# ee107_mcu_fpga_connector_board.net
KiCad netlist of a schematic drawn in Altium Designer
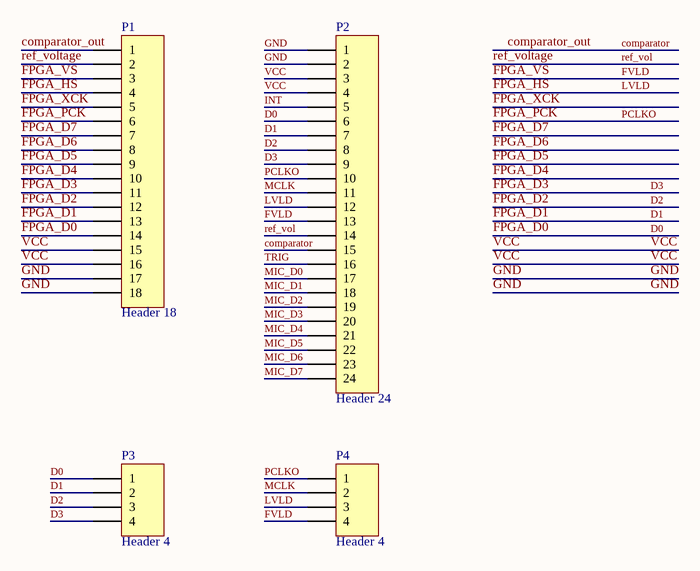
[diagram p0: ee107_mcu_fpga_connector_board.SchDoc]

(export (version "E")
  (design (tool "Eeschema 10.0.6"))
  (components
    (comp (ref "P1")
      (value "Header 18")
      (footprint "HDR1X18")
      (description "Header, 18-Pin")
      (fields (field (name "PUBLISHER") "Altium Limited"))
      (libsource (lib "Miscellaneous Connectors") (part "Header 18"))
    )
    (comp (ref "P2")
      (value "Header 24")
      (footprint "HDR1X24")
      (description "Header, 24-Pin")
      (fields (field (name "PUBLISHER") "Altium Limited"))
      (libsource (lib "Miscellaneous Connectors") (part "Header 24"))
    )
    (comp (ref "P3")
      (value "Header 4")
      (footprint "HDR1X4")
      (description "Header, 4-Pin")
      (fields (field (name "PUBLISHER") "Altium Limited"))
      (libsource (lib "Miscellaneous Connectors") (part "Header 4"))
    )
    (comp (ref "P4")
      (value "Header 4")
      (footprint "HDR1X4")
      (description "Header, 4-Pin")
      (fields (field (name "PUBLISHER") "Altium Limited"))
      (libsource (lib "Miscellaneous Connectors") (part "Header 4"))
    )
  )
  (nets
    (net (code "1") (name "/D0") (class "Default")
      (node (ref "P1") (pin "14") (pinfunction "14_14") (pintype "passive"))
      (node (ref "P2") (pin "6") (pinfunction "6_6") (pintype "passive"))
      (node (ref "P3") (pin "1") (pinfunction "1_1") (pintype "passive"))
    )
    (net (code "2") (name "/D1") (class "Default")
      (node (ref "P1") (pin "13") (pinfunction "13_13") (pintype "passive"))
      (node (ref "P2") (pin "7") (pinfunction "7_7") (pintype "passive"))
      (node (ref "P3") (pin "2") (pinfunction "2_2") (pintype "passive"))
    )
    (net (code "3") (name "/D2") (class "Default")
      (node (ref "P1") (pin "12") (pinfunction "12_12") (pintype "passive"))
      (node (ref "P2") (pin "8") (pinfunction "8_8") (pintype "passive"))
      (node (ref "P3") (pin "3") (pinfunction "3_3") (pintype "passive"))
    )
    (net (code "4") (name "/D3") (class "Default")
      (node (ref "P1") (pin "11") (pinfunction "11_11") (pintype "passive"))
      (node (ref "P2") (pin "9") (pinfunction "9_9") (pintype "passive"))
      (node (ref "P3") (pin "4") (pinfunction "4_4") (pintype "passive"))
    )
    (net (code "5") (name "/FPGA_D4") (class "Default")
      (node (ref "P1") (pin "10") (pinfunction "10_10") (pintype "passive"))
    )
    (net (code "6") (name "/FPGA_D5") (class "Default")
      (node (ref "P1") (pin "9") (pinfunction "9_9") (pintype "passive"))
    )
    (net (code "7") (name "/FPGA_D6") (class "Default")
      (node (ref "P1") (pin "8") (pinfunction "8_8") (pintype "passive"))
    )
    (net (code "8") (name "/FPGA_D7") (class "Default")
      (node (ref "P1") (pin "7") (pinfunction "7_7") (pintype "passive"))
    )
    (net (code "9") (name "/FPGA_HS") (class "Default")
      (node (ref "P1") (pin "4") (pinfunction "4_4") (pintype "passive"))
      (node (ref "P2") (pin "12") (pinfunction "12_12") (pintype "passive"))
      (node (ref "P4") (pin "3") (pinfunction "3_3") (pintype "passive"))
    )
    (net (code "10") (name "/FPGA_PCK") (class "Default")
      (node (ref "P1") (pin "6") (pinfunction "6_6") (pintype "passive"))
      (node (ref "P2") (pin "10") (pinfunction "10_10") (pintype "passive"))
      (node (ref "P4") (pin "1") (pinfunction "1_1") (pintype "passive"))
    )
    (net (code "11") (name "/FPGA_VS") (class "Default")
      (node (ref "P1") (pin "3") (pinfunction "3_3") (pintype "passive"))
      (node (ref "P2") (pin "13") (pinfunction "13_13") (pintype "passive"))
      (node (ref "P4") (pin "4") (pinfunction "4_4") (pintype "passive"))
    )
    (net (code "12") (name "/FPGA_XCK") (class "Default")
      (node (ref "P1") (pin "5") (pinfunction "5_5") (pintype "passive"))
    )
    (net (code "13") (name "/GND") (class "Default")
      (node (ref "P1") (pin "17") (pinfunction "17_17") (pintype "passive"))
      (node (ref "P1") (pin "18") (pinfunction "18_18") (pintype "passive"))
      (node (ref "P2") (pin "1") (pinfunction "1_1") (pintype "passive"))
      (node (ref "P2") (pin "2") (pinfunction "2_2") (pintype "passive"))
    )
    (net (code "14") (name "/INT") (class "Default")
      (node (ref "P2") (pin "5") (pinfunction "5_5") (pintype "passive"))
    )
    (net (code "15") (name "/MCLK") (class "Default")
      (node (ref "P2") (pin "11") (pinfunction "11_11") (pintype "passive"))
      (node (ref "P4") (pin "2") (pinfunction "2_2") (pintype "passive"))
    )
    (net (code "16") (name "/MIC_D0") (class "Default")
      (node (ref "P2") (pin "17") (pinfunction "17_17") (pintype "passive"))
    )
    (net (code "17") (name "/MIC_D1") (class "Default")
      (node (ref "P2") (pin "18") (pinfunction "18_18") (pintype "passive"))
    )
    (net (code "18") (name "/MIC_D2") (class "Default")
      (node (ref "P2") (pin "19") (pinfunction "19_19") (pintype "passive"))
    )
    (net (code "19") (name "/MIC_D3") (class "Default")
      (node (ref "P2") (pin "20") (pinfunction "20_20") (pintype "passive"))
    )
    (net (code "20") (name "/MIC_D4") (class "Default")
      (node (ref "P2") (pin "21") (pinfunction "21_21") (pintype "passive"))
    )
    (net (code "21") (name "/MIC_D5") (class "Default")
      (node (ref "P2") (pin "22") (pinfunction "22_22") (pintype "passive"))
    )
    (net (code "22") (name "/MIC_D6") (class "Default")
      (node (ref "P2") (pin "23") (pinfunction "23_23") (pintype "passive"))
    )
    (net (code "23") (name "/MIC_D7") (class "Default")
      (node (ref "P2") (pin "24") (pinfunction "24_24") (pintype "passive"))
    )
    (net (code "24") (name "/TRIG") (class "Default")
      (node (ref "P2") (pin "16") (pinfunction "16_16") (pintype "passive"))
    )
    (net (code "25") (name "/VCC") (class "Default")
      (node (ref "P1") (pin "15") (pinfunction "15_15") (pintype "passive"))
      (node (ref "P1") (pin "16") (pinfunction "16_16") (pintype "passive"))
      (node (ref "P2") (pin "3") (pinfunction "3_3") (pintype "passive"))
      (node (ref "P2") (pin "4") (pinfunction "4_4") (pintype "passive"))
    )
    (net (code "26") (name "/comparator") (class "Default")
      (node (ref "P1") (pin "1") (pinfunction "1_1") (pintype "passive"))
      (node (ref "P2") (pin "15") (pinfunction "15_15") (pintype "passive"))
    )
    (net (code "27") (name "/ref_vol") (class "Default")
      (node (ref "P1") (pin "2") (pinfunction "2_2") (pintype "passive"))
      (node (ref "P2") (pin "14") (pinfunction "14_14") (pintype "passive"))
    )
  )
)
